# hat_v2.net
KiCad netlist of a schematic drawn in EAGLE
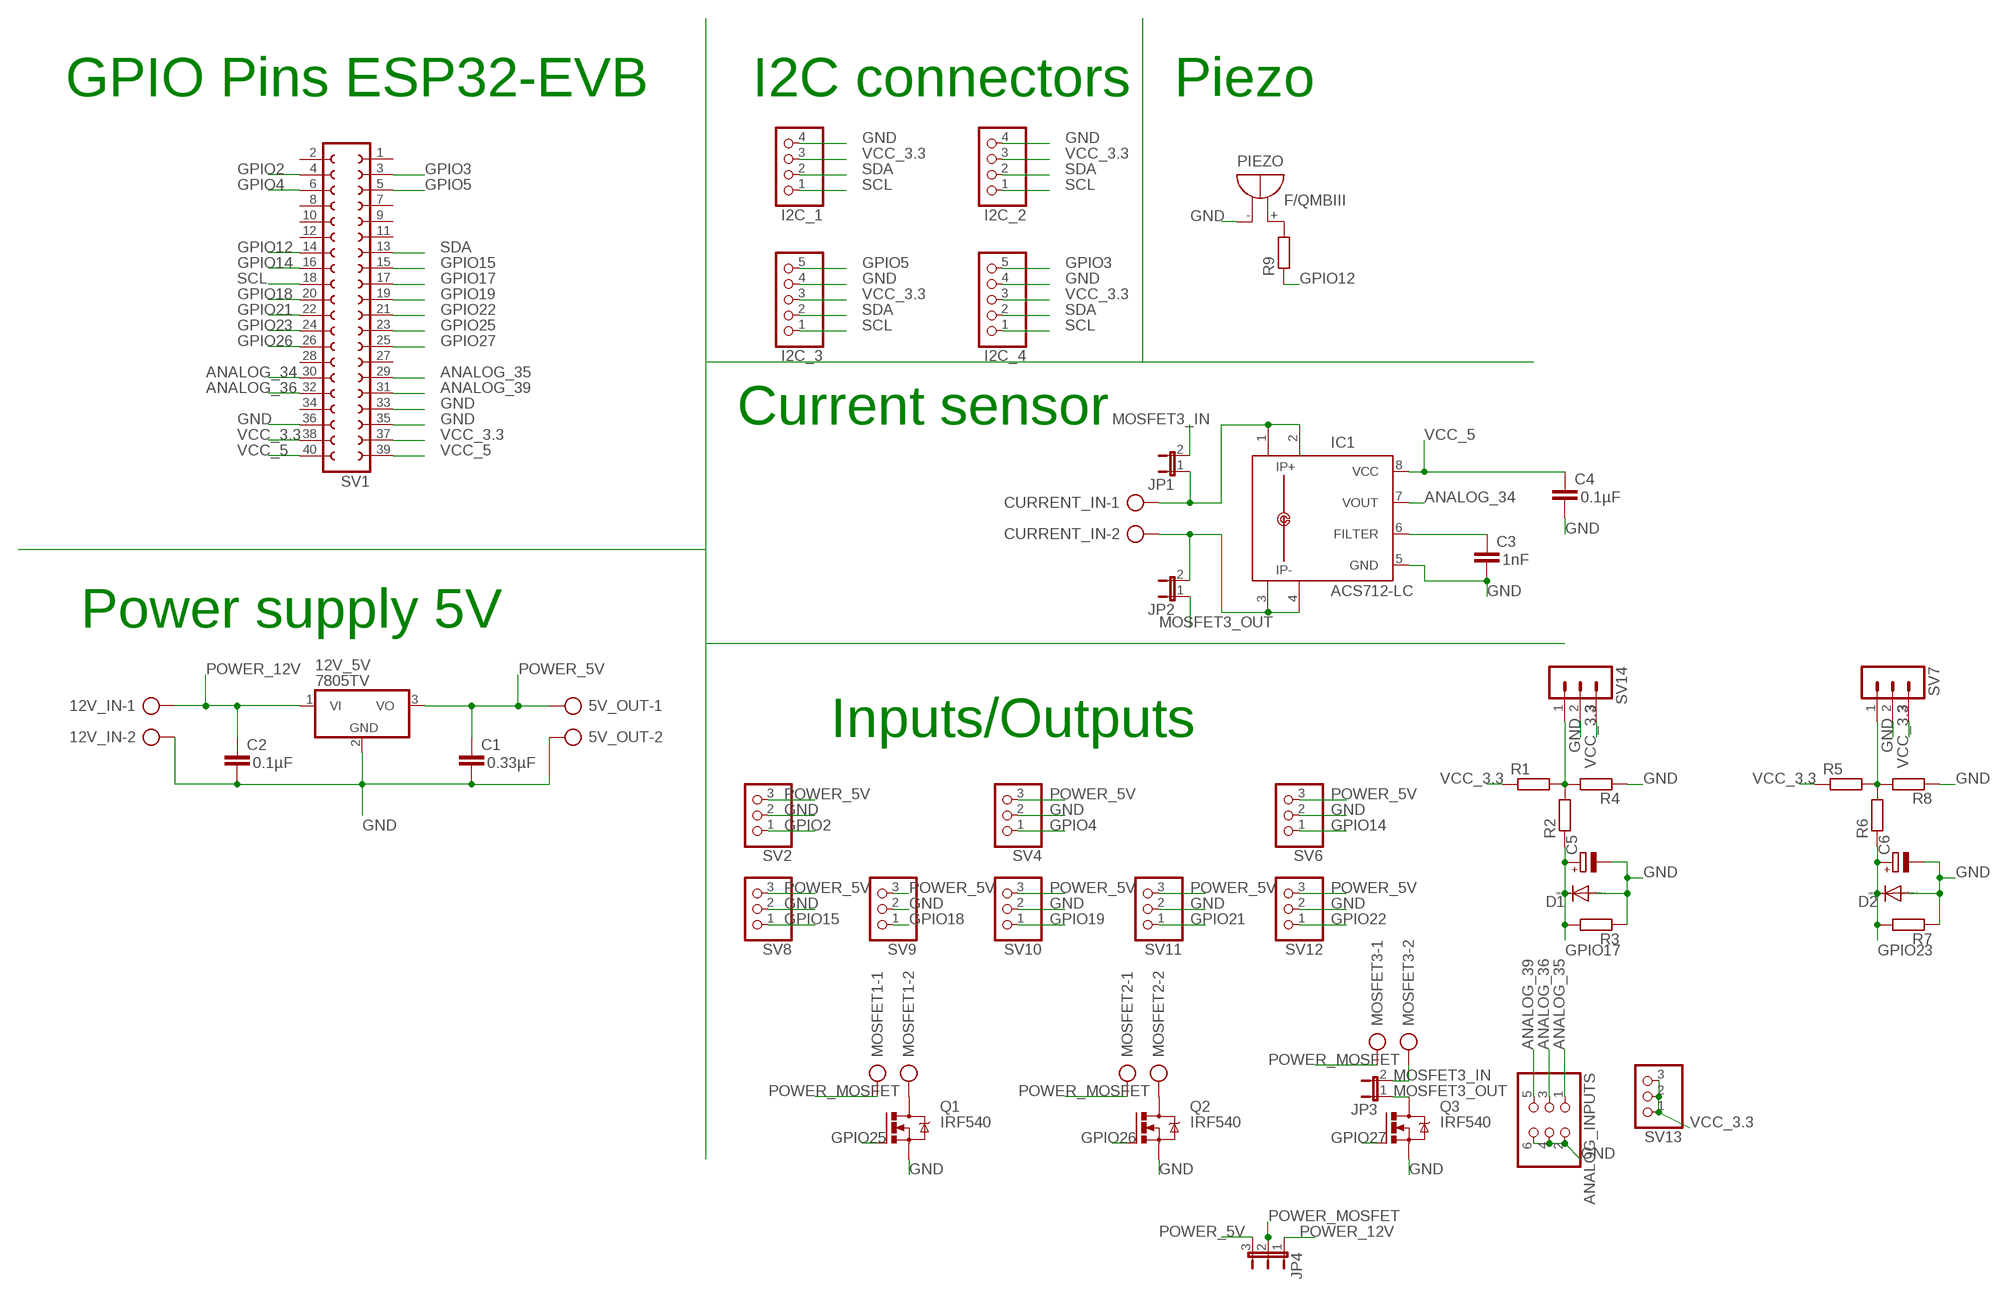
[diagram p0: schematic, sheet 1]

(export (version "E")
  (design (tool "Eeschema 10.0.6"))
  (components
    (comp (ref "5V_OUT")
      (value "AK500/2")
      (footprint "eagle-import:AK500_2")
      (libsource (lib "eagle-import") (part "AK500/2"))
    )
    (comp (ref "12V_5V")
      (value "7805TV")
      (footprint "eagle-import:TO220V")
      (libsource (lib "eagle-import") (part "78TV05"))
    )
    (comp (ref "12V_IN")
      (value "AK500/2")
      (footprint "eagle-import:AK500_2")
      (libsource (lib "eagle-import") (part "AK500/2"))
    )
    (comp (ref "ANALOG_INPUTS")
      (value "PINHD-2X3")
      (footprint "eagle-import:2X03")
      (libsource (lib "eagle-import") (part "PINHD-2X3"))
    )
    (comp (ref "C1")
      (value "C-EU050-050X075")
      (footprint "eagle-import:C050-050X075")
      (fields (field (name "C1") "0.33µF"))
      (libsource (lib "eagle-import") (part "resistor_348_C-EU050-050X075"))
    )
    (comp (ref "C2")
      (value "C-EU050-035X075")
      (footprint "eagle-import:C050-035X075")
      (fields (field (name "C2") "0.1µF"))
      (libsource (lib "eagle-import") (part "resistor_348_C-EU050-035X075"))
    )
    (comp (ref "C3")
      (value "C-EU025-025X050")
      (footprint "eagle-import:C025-025X050")
      (fields (field (name "SPICEPREFIX") "C") (field (name "SPICEPREFIX_1") "1nF"))
      (libsource (lib "eagle-import") (part "C-EU025-025X050"))
    )
    (comp (ref "C4")
      (value "C-EU025-025X050")
      (footprint "eagle-import:C025-025X050")
      (fields (field (name "SPICEPREFIX") "C") (field (name "SPICEPREFIX_1") "0.1µF"))
      (libsource (lib "eagle-import") (part "C-EU025-025X050"))
    )
    (comp (ref "C5")
      (value "CPOL-EUE2.5-6")
      (footprint "eagle-import:E2,5-6")
      (libsource (lib "eagle-import") (part "CPOL-EUE2.5-6"))
    )
    (comp (ref "C6")
      (value "CPOL-EUE2.5-6")
      (footprint "eagle-import:E2,5-6")
      (libsource (lib "eagle-import") (part "CPOL-EUE2.5-6"))
    )
    (comp (ref "CURRENT_IN")
      (value "AK500/2")
      (footprint "eagle-import:AK500_2")
      (libsource (lib "eagle-import") (part "AK500/2"))
    )
    (comp (ref "D1")
      (value "DIODE-C1702-05")
      (footprint "eagle-import:C1702-05")
      (libsource (lib "eagle-import") (part "DIODE-C1702-05"))
    )
    (comp (ref "D2")
      (value "DIODE-C1702-05")
      (footprint "eagle-import:C1702-05")
      (libsource (lib "eagle-import") (part "DIODE-C1702-05"))
    )
    (comp (ref "I2C_1")
      (value "PINHD-1X4")
      (footprint "eagle-import:1X04")
      (libsource (lib "eagle-import") (part "PINHD-1X4"))
    )
    (comp (ref "I2C_2")
      (value "PINHD-1X4")
      (footprint "eagle-import:1X04")
      (libsource (lib "eagle-import") (part "PINHD-1X4"))
    )
    (comp (ref "I2C_3")
      (value "PINHD-1X5")
      (footprint "eagle-import:1X05")
      (libsource (lib "eagle-import") (part "PINHD-1X5"))
    )
    (comp (ref "I2C_4")
      (value "PINHD-1X5")
      (footprint "eagle-import:1X05")
      (libsource (lib "eagle-import") (part "PINHD-1X5"))
    )
    (comp (ref "IC1")
      (value "ACS712-LC")
      (footprint "eagle-import:SOIC8")
      (libsource (lib "eagle-import") (part "ACS712-LC"))
    )
    (comp (ref "JP1")
      (value "JP1E")
      (footprint "eagle-import:JP1")
      (libsource (lib "eagle-import") (part "JP1E"))
    )
    (comp (ref "JP2")
      (value "JP1E")
      (footprint "eagle-import:JP1")
      (libsource (lib "eagle-import") (part "JP1E"))
    )
    (comp (ref "JP3")
      (value "JP1E")
      (footprint "eagle-import:JP1")
      (libsource (lib "eagle-import") (part "JP1E"))
    )
    (comp (ref "JP4")
      (value "JP2E")
      (footprint "eagle-import:JP2")
      (libsource (lib "eagle-import") (part "JP2E"))
    )
    (comp (ref "MOSFET1")
      (value "AK500/2")
      (footprint "eagle-import:AK500_2")
      (libsource (lib "eagle-import") (part "AK500/2"))
    )
    (comp (ref "MOSFET2")
      (value "AK500/2")
      (footprint "eagle-import:AK500_2")
      (libsource (lib "eagle-import") (part "AK500/2"))
    )
    (comp (ref "MOSFET3")
      (value "AK500/2")
      (footprint "eagle-import:AK500_2")
      (libsource (lib "eagle-import") (part "AK500/2"))
    )
    (comp (ref "PIEZO")
      (value "F/QMBIII")
      (footprint "eagle-import:F_QMBIII")
      (libsource (lib "eagle-import") (part "F/QMBIII"))
    )
    (comp (ref "Q1")
      (value "IRF540")
      (footprint "eagle-import:TO220BV")
      (libsource (lib "eagle-import") (part "IRF540"))
    )
    (comp (ref "Q2")
      (value "IRF540")
      (footprint "eagle-import:TO220BV")
      (libsource (lib "eagle-import") (part "IRF540"))
    )
    (comp (ref "Q3")
      (value "IRF540")
      (footprint "eagle-import:TO220BV")
      (libsource (lib "eagle-import") (part "IRF540"))
    )
    (comp (ref "R1")
      (value "R-EU_0207/2V")
      (footprint "eagle-import:0207_2V")
      (libsource (lib "eagle-import") (part "R-EU_0207/2V"))
    )
    (comp (ref "R2")
      (value "R-EU_0207/2V")
      (footprint "eagle-import:0207_2V")
      (libsource (lib "eagle-import") (part "R-EU_0207/2V"))
    )
    (comp (ref "R3")
      (value "R-EU_0207/2V")
      (footprint "eagle-import:0207_2V")
      (libsource (lib "eagle-import") (part "R-EU_0207/2V"))
    )
    (comp (ref "R4")
      (value "R-EU_0617/5V")
      (footprint "eagle-import:0617V")
      (libsource (lib "eagle-import") (part "R-EU_0617/5V"))
    )
    (comp (ref "R5")
      (value "R-EU_0207/2V")
      (footprint "eagle-import:0207_2V")
      (libsource (lib "eagle-import") (part "R-EU_0207/2V"))
    )
    (comp (ref "R6")
      (value "R-EU_0207/2V")
      (footprint "eagle-import:0207_2V")
      (libsource (lib "eagle-import") (part "R-EU_0207/2V"))
    )
    (comp (ref "R7")
      (value "R-EU_0207/2V")
      (footprint "eagle-import:0207_2V")
      (libsource (lib "eagle-import") (part "R-EU_0207/2V"))
    )
    (comp (ref "R8")
      (value "R-EU_0617/5V")
      (footprint "eagle-import:0617V")
      (libsource (lib "eagle-import") (part "R-EU_0617/5V"))
    )
    (comp (ref "R9")
      (value "R-EU_0207/5V")
      (footprint "eagle-import:0207_5V")
      (libsource (lib "eagle-import") (part "R-EU_0207/5V"))
    )
    (comp (ref "SV1")
      (value "FE20-2")
      (footprint "eagle-import:FE20-2")
      (libsource (lib "eagle-import") (part "FE20-2"))
    )
    (comp (ref "SV2")
      (value "PINHD-1X3")
      (footprint "eagle-import:1X03")
      (fields (field (name "SPICEPREFIX") "J"))
      (libsource (lib "eagle-import") (part "PINHD-1X3"))
    )
    (comp (ref "SV4")
      (value "PINHD-1X3")
      (footprint "eagle-import:1X03")
      (fields (field (name "SPICEPREFIX") "J"))
      (libsource (lib "eagle-import") (part "PINHD-1X3"))
    )
    (comp (ref "SV6")
      (value "PINHD-1X3")
      (footprint "eagle-import:1X03")
      (fields (field (name "SPICEPREFIX") "J"))
      (libsource (lib "eagle-import") (part "PINHD-1X3"))
    )
    (comp (ref "SV7")
      (value "MA03-1")
      (footprint "eagle-import:MA03-1")
      (fields (field (name "SPICEPREFIX") "J"))
      (libsource (lib "eagle-import") (part "MA03-1"))
    )
    (comp (ref "SV8")
      (value "PINHD-1X3")
      (footprint "eagle-import:1X03")
      (libsource (lib "eagle-import") (part "PINHD-1X3"))
    )
    (comp (ref "SV9")
      (value "PINHD-1X3")
      (footprint "eagle-import:1X03")
      (fields (field (name "SPICEPREFIX") "J"))
      (libsource (lib "eagle-import") (part "PINHD-1X3"))
    )
    (comp (ref "SV10")
      (value "PINHD-1X3")
      (footprint "eagle-import:1X03")
      (fields (field (name "SPICEPREFIX") "J"))
      (libsource (lib "eagle-import") (part "PINHD-1X3"))
    )
    (comp (ref "SV11")
      (value "PINHD-1X3")
      (footprint "eagle-import:1X03")
      (fields (field (name "SPICEPREFIX") "J"))
      (libsource (lib "eagle-import") (part "PINHD-1X3"))
    )
    (comp (ref "SV12")
      (value "PINHD-1X3")
      (footprint "eagle-import:1X03")
      (fields (field (name "SPICEPREFIX") "J"))
      (libsource (lib "eagle-import") (part "PINHD-1X3"))
    )
    (comp (ref "SV13")
      (value "PINHD-1X3")
      (footprint "eagle-import:1X03")
      (libsource (lib "eagle-import") (part "PINHD-1X3"))
    )
    (comp (ref "SV14")
      (value "MA03-1")
      (footprint "eagle-import:MA03-1")
      (fields (field (name "SPICEPREFIX") "J"))
      (libsource (lib "eagle-import") (part "MA03-1"))
    )
  )
  (nets
    (net (code "1") (name "/ANALOG_34") (class "Default")
      (node (ref "IC1") (pin "7") (pinfunction "VOUT_7") (pintype "output"))
      (node (ref "SV1") (pin "30") (pinfunction "30_30") (pintype "passive"))
    )
    (net (code "2") (name "/ANALOG_35") (class "Default")
      (node (ref "ANALOG_INPUTS") (pin "1") (pinfunction "1_1") (pintype "passive"))
      (node (ref "SV1") (pin "29") (pinfunction "29_29") (pintype "passive"))
    )
    (net (code "3") (name "/ANALOG_36") (class "Default")
      (node (ref "ANALOG_INPUTS") (pin "3") (pinfunction "3_3") (pintype "passive"))
      (node (ref "SV1") (pin "32") (pinfunction "32_32") (pintype "passive"))
    )
    (net (code "4") (name "/ANALOG_39") (class "Default")
      (node (ref "ANALOG_INPUTS") (pin "5") (pinfunction "5_5") (pintype "passive"))
      (node (ref "SV1") (pin "31") (pinfunction "31_31") (pintype "passive"))
    )
    (net (code "5") (name "/GND") (class "Default")
      (node (ref "12V_5V") (pin "2") (pinfunction "GND_2") (pintype "passive"))
      (node (ref "12V_IN") (pin "2") (pinfunction "KL_2") (pintype "passive"))
      (node (ref "5V_OUT") (pin "2") (pinfunction "KL_2") (pintype "passive"))
      (node (ref "ANALOG_INPUTS") (pin "2") (pinfunction "2_2") (pintype "passive"))
      (node (ref "ANALOG_INPUTS") (pin "4") (pinfunction "4_4") (pintype "passive"))
      (node (ref "ANALOG_INPUTS") (pin "6") (pinfunction "6_6") (pintype "passive"))
      (node (ref "C1") (pin "2") (pinfunction "2_2") (pintype "passive"))
      (node (ref "C2") (pin "2") (pinfunction "2_2") (pintype "passive"))
      (node (ref "C3") (pin "2") (pinfunction "2_2") (pintype "passive"))
      (node (ref "C4") (pin "2") (pinfunction "2_2") (pintype "passive"))
      (node (ref "C5") (pin "-") (pinfunction "-_-") (pintype "passive"))
      (node (ref "C6") (pin "-") (pinfunction "-_-") (pintype "passive"))
      (node (ref "D1") (pin "A") (pinfunction "A_A") (pintype "passive"))
      (node (ref "D2") (pin "A") (pinfunction "A_A") (pintype "passive"))
      (node (ref "I2C_1") (pin "4") (pinfunction "4_4") (pintype "passive"))
      (node (ref "I2C_2") (pin "4") (pinfunction "4_4") (pintype "passive"))
      (node (ref "I2C_3") (pin "4") (pinfunction "4_4") (pintype "passive"))
      (node (ref "I2C_4") (pin "4") (pinfunction "4_4") (pintype "passive"))
      (node (ref "IC1") (pin "5") (pinfunction "GND_5") (pintype "power_in"))
      (node (ref "PIEZO") (pin "-") (pinfunction "+_-") (pintype "passive"))
      (node (ref "Q1") (pin "S") (pinfunction "S_S") (pintype "passive"))
      (node (ref "Q2") (pin "S") (pinfunction "S_S") (pintype "passive"))
      (node (ref "Q3") (pin "S") (pinfunction "S_S") (pintype "passive"))
      (node (ref "R3") (pin "1") (pinfunction "1_1") (pintype "passive"))
      (node (ref "R4") (pin "1") (pinfunction "1_1") (pintype "passive"))
      (node (ref "R7") (pin "1") (pinfunction "1_1") (pintype "passive"))
      (node (ref "R8") (pin "1") (pinfunction "1_1") (pintype "passive"))
      (node (ref "SV1") (pin "33") (pinfunction "33_33") (pintype "passive"))
      (node (ref "SV1") (pin "35") (pinfunction "35_35") (pintype "passive"))
      (node (ref "SV1") (pin "36") (pinfunction "36_36") (pintype "passive"))
      (node (ref "SV10") (pin "2") (pinfunction "2_2") (pintype "passive"))
      (node (ref "SV11") (pin "2") (pinfunction "2_2") (pintype "passive"))
      (node (ref "SV12") (pin "2") (pinfunction "2_2") (pintype "passive"))
      (node (ref "SV14") (pin "2") (pinfunction "2_2") (pintype "passive"))
      (node (ref "SV2") (pin "2") (pinfunction "2_2") (pintype "passive"))
      (node (ref "SV4") (pin "2") (pinfunction "2_2") (pintype "passive"))
      (node (ref "SV6") (pin "2") (pinfunction "2_2") (pintype "passive"))
      (node (ref "SV7") (pin "2") (pinfunction "2_2") (pintype "passive"))
      (node (ref "SV8") (pin "2") (pinfunction "2_2") (pintype "passive"))
      (node (ref "SV9") (pin "2") (pinfunction "2_2") (pintype "passive"))
    )
    (net (code "6") (name "/GPIO2") (class "Default")
      (node (ref "SV1") (pin "4") (pinfunction "4_4") (pintype "passive"))
      (node (ref "SV2") (pin "1") (pinfunction "1_1") (pintype "passive"))
    )
    (net (code "7") (name "/GPIO3") (class "Default")
      (node (ref "I2C_4") (pin "5") (pinfunction "5_5") (pintype "passive"))
      (node (ref "SV1") (pin "3") (pinfunction "3_3") (pintype "passive"))
    )
    (net (code "8") (name "/GPIO4") (class "Default")
      (node (ref "SV1") (pin "6") (pinfunction "6_6") (pintype "passive"))
      (node (ref "SV4") (pin "1") (pinfunction "1_1") (pintype "passive"))
    )
    (net (code "9") (name "/GPIO5") (class "Default")
      (node (ref "I2C_3") (pin "5") (pinfunction "5_5") (pintype "passive"))
      (node (ref "SV1") (pin "5") (pinfunction "5_5") (pintype "passive"))
    )
    (net (code "10") (name "/GPIO12") (class "Default")
      (node (ref "R9") (pin "1") (pinfunction "1_1") (pintype "passive"))
      (node (ref "SV1") (pin "14") (pinfunction "14_14") (pintype "passive"))
    )
    (net (code "11") (name "/GPIO14") (class "Default")
      (node (ref "SV1") (pin "16") (pinfunction "16_16") (pintype "passive"))
      (node (ref "SV6") (pin "1") (pinfunction "1_1") (pintype "passive"))
    )
    (net (code "12") (name "/GPIO15") (class "Default")
      (node (ref "SV1") (pin "15") (pinfunction "15_15") (pintype "passive"))
      (node (ref "SV8") (pin "1") (pinfunction "1_1") (pintype "passive"))
    )
    (net (code "13") (name "/GPIO17") (class "Default")
      (node (ref "C5") (pin "+") (pinfunction "+_+") (pintype "passive"))
      (node (ref "D1") (pin "C") (pinfunction "C_C") (pintype "passive"))
      (node (ref "R2") (pin "1") (pinfunction "1_1") (pintype "passive"))
      (node (ref "R3") (pin "2") (pinfunction "2_2") (pintype "passive"))
      (node (ref "SV1") (pin "17") (pinfunction "17_17") (pintype "passive"))
    )
    (net (code "14") (name "/GPIO18") (class "Default")
      (node (ref "SV1") (pin "20") (pinfunction "20_20") (pintype "passive"))
      (node (ref "SV9") (pin "1") (pinfunction "1_1") (pintype "passive"))
    )
    (net (code "15") (name "/GPIO19") (class "Default")
      (node (ref "SV1") (pin "19") (pinfunction "19_19") (pintype "passive"))
      (node (ref "SV10") (pin "1") (pinfunction "1_1") (pintype "passive"))
    )
    (net (code "16") (name "/GPIO21") (class "Default")
      (node (ref "SV1") (pin "22") (pinfunction "22_22") (pintype "passive"))
      (node (ref "SV11") (pin "1") (pinfunction "1_1") (pintype "passive"))
    )
    (net (code "17") (name "/GPIO22") (class "Default")
      (node (ref "SV1") (pin "21") (pinfunction "21_21") (pintype "passive"))
      (node (ref "SV12") (pin "1") (pinfunction "1_1") (pintype "passive"))
    )
    (net (code "18") (name "/GPIO23") (class "Default")
      (node (ref "C6") (pin "+") (pinfunction "+_+") (pintype "passive"))
      (node (ref "D2") (pin "C") (pinfunction "C_C") (pintype "passive"))
      (node (ref "R6") (pin "1") (pinfunction "1_1") (pintype "passive"))
      (node (ref "R7") (pin "2") (pinfunction "2_2") (pintype "passive"))
      (node (ref "SV1") (pin "24") (pinfunction "24_24") (pintype "passive"))
    )
    (net (code "19") (name "/GPIO25") (class "Default")
      (node (ref "Q1") (pin "G") (pinfunction "G_G") (pintype "passive"))
      (node (ref "SV1") (pin "23") (pinfunction "23_23") (pintype "passive"))
    )
    (net (code "20") (name "/GPIO26") (class "Default")
      (node (ref "Q2") (pin "G") (pinfunction "G_G") (pintype "passive"))
      (node (ref "SV1") (pin "26") (pinfunction "26_26") (pintype "passive"))
    )
    (net (code "21") (name "/GPIO27") (class "Default")
      (node (ref "Q3") (pin "G") (pinfunction "G_G") (pintype "passive"))
      (node (ref "SV1") (pin "25") (pinfunction "25_25") (pintype "passive"))
    )
    (net (code "22") (name "/MOSFET3_IN") (class "Default")
      (node (ref "JP1") (pin "2") (pinfunction "2_2") (pintype "passive"))
      (node (ref "JP3") (pin "2") (pinfunction "2_2") (pintype "passive"))
      (node (ref "MOSFET3") (pin "2") (pinfunction "KL_2") (pintype "passive"))
    )
    (net (code "23") (name "/MOSFET3_OUT") (class "Default")
      (node (ref "JP2") (pin "1") (pinfunction "1_1") (pintype "passive"))
      (node (ref "JP3") (pin "1") (pinfunction "1_1") (pintype "passive"))
      (node (ref "Q3") (pin "D") (pinfunction "D_D") (pintype "passive"))
    )
    (net (code "24") (name "/POWER_5V") (class "Default")
      (node (ref "12V_5V") (pin "3") (pinfunction "VO_3") (pintype "passive"))
      (node (ref "5V_OUT") (pin "1") (pinfunction "KL_1") (pintype "passive"))
      (node (ref "C1") (pin "1") (pinfunction "1_1") (pintype "passive"))
      (node (ref "JP4") (pin "3") (pinfunction "3_3") (pintype "passive"))
      (node (ref "SV10") (pin "3") (pinfunction "3_3") (pintype "passive"))
      (node (ref "SV11") (pin "3") (pinfunction "3_3") (pintype "passive"))
      (node (ref "SV12") (pin "3") (pinfunction "3_3") (pintype "passive"))
      (node (ref "SV2") (pin "3") (pinfunction "3_3") (pintype "passive"))
      (node (ref "SV4") (pin "3") (pinfunction "3_3") (pintype "passive"))
      (node (ref "SV6") (pin "3") (pinfunction "3_3") (pintype "passive"))
      (node (ref "SV8") (pin "3") (pinfunction "3_3") (pintype "passive"))
      (node (ref "SV9") (pin "3") (pinfunction "3_3") (pintype "passive"))
    )
    (net (code "25") (name "/POWER_12V") (class "Default")
      (node (ref "12V_5V") (pin "1") (pinfunction "VI_1") (pintype "input"))
      (node (ref "12V_IN") (pin "1") (pinfunction "KL_1") (pintype "passive"))
      (node (ref "C2") (pin "1") (pinfunction "1_1") (pintype "passive"))
      (node (ref "JP4") (pin "1") (pinfunction "1_1") (pintype "passive"))
    )
    (net (code "26") (name "/POWER_MOSFET") (class "Default")
      (node (ref "JP4") (pin "2") (pinfunction "2_2") (pintype "passive"))
      (node (ref "MOSFET1") (pin "1") (pinfunction "KL_1") (pintype "passive"))
      (node (ref "MOSFET2") (pin "1") (pinfunction "KL_1") (pintype "passive"))
      (node (ref "MOSFET3") (pin "1") (pinfunction "KL_1") (pintype "passive"))
    )
    (net (code "27") (name "/SCL") (class "Default")
      (node (ref "I2C_1") (pin "1") (pinfunction "1_1") (pintype "passive"))
      (node (ref "I2C_2") (pin "1") (pinfunction "1_1") (pintype "passive"))
      (node (ref "I2C_3") (pin "1") (pinfunction "1_1") (pintype "passive"))
      (node (ref "I2C_4") (pin "1") (pinfunction "1_1") (pintype "passive"))
      (node (ref "SV1") (pin "18") (pinfunction "18_18") (pintype "passive"))
    )
    (net (code "28") (name "/SDA") (class "Default")
      (node (ref "I2C_1") (pin "2") (pinfunction "2_2") (pintype "passive"))
      (node (ref "I2C_2") (pin "2") (pinfunction "2_2") (pintype "passive"))
      (node (ref "I2C_3") (pin "2") (pinfunction "2_2") (pintype "passive"))
      (node (ref "I2C_4") (pin "2") (pinfunction "2_2") (pintype "passive"))
      (node (ref "SV1") (pin "13") (pinfunction "13_13") (pintype "passive"))
    )
    (net (code "29") (name "/VCC_3.3") (class "Default")
      (node (ref "I2C_1") (pin "3") (pinfunction "3_3") (pintype "passive"))
      (node (ref "I2C_2") (pin "3") (pinfunction "3_3") (pintype "passive"))
      (node (ref "I2C_3") (pin "3") (pinfunction "3_3") (pintype "passive"))
      (node (ref "I2C_4") (pin "3") (pinfunction "3_3") (pintype "passive"))
      (node (ref "R1") (pin "1") (pinfunction "1_1") (pintype "passive"))
      (node (ref "R5") (pin "1") (pinfunction "1_1") (pintype "passive"))
      (node (ref "SV1") (pin "37") (pinfunction "37_37") (pintype "passive"))
      (node (ref "SV1") (pin "38") (pinfunction "38_38") (pintype "passive"))
      (node (ref "SV13") (pin "1") (pinfunction "1_1") (pintype "passive"))
      (node (ref "SV13") (pin "2") (pinfunction "2_2") (pintype "passive"))
      (node (ref "SV13") (pin "3") (pinfunction "3_3") (pintype "passive"))
      (node (ref "SV14") (pin "3") (pinfunction "3_3") (pintype "passive"))
      (node (ref "SV7") (pin "3") (pinfunction "3_3") (pintype "passive"))
    )
    (net (code "30") (name "/VCC_5") (class "Default")
      (node (ref "C4") (pin "1") (pinfunction "1_1") (pintype "passive"))
      (node (ref "IC1") (pin "8") (pinfunction "VCC_8") (pintype "power_in"))
      (node (ref "SV1") (pin "39") (pinfunction "39_39") (pintype "passive"))
      (node (ref "SV1") (pin "40") (pinfunction "40_40") (pintype "passive"))
    )
    (net (code "31") (name "Net-(CURRENT_INA-KL)") (class "Default")
      (node (ref "CURRENT_IN") (pin "1") (pinfunction "KL_1") (pintype "passive"))
      (node (ref "IC1") (pin "1") (pinfunction "IP+_1") (pintype "passive"))
      (node (ref "IC1") (pin "2") (pinfunction "IP+1_2") (pintype "passive"))
      (node (ref "JP1") (pin "1") (pinfunction "1_1") (pintype "passive"))
    )
    (net (code "32") (name "Net-(CURRENT_INB-KL)") (class "Default")
      (node (ref "CURRENT_IN") (pin "2") (pinfunction "KL_2") (pintype "passive"))
      (node (ref "IC1") (pin "3") (pinfunction "IP-_3") (pintype "passive"))
      (node (ref "IC1") (pin "4") (pinfunction "IP-1_4") (pintype "passive"))
      (node (ref "JP2") (pin "2") (pinfunction "2_2") (pintype "passive"))
    )
    (net (code "33") (name "Net-(IC1-FILTER)") (class "Default")
      (node (ref "C3") (pin "1") (pinfunction "1_1") (pintype "passive"))
      (node (ref "IC1") (pin "6") (pinfunction "FILTER_6") (pintype "bidirectional"))
    )
    (net (code "34") (name "Net-(MOSFET1B-KL)") (class "Default")
      (node (ref "MOSFET1") (pin "2") (pinfunction "KL_2") (pintype "passive"))
      (node (ref "Q1") (pin "D") (pinfunction "D_D") (pintype "passive"))
    )
    (net (code "35") (name "Net-(MOSFET2B-KL)") (class "Default")
      (node (ref "MOSFET2") (pin "2") (pinfunction "KL_2") (pintype "passive"))
      (node (ref "Q2") (pin "D") (pinfunction "D_D") (pintype "passive"))
    )
    (net (code "36") (name "Net-(PIEZO--)") (class "Default")
      (node (ref "PIEZO") (pin "+") (pinfunction "-_+") (pintype "passive"))
      (node (ref "R9") (pin "2") (pinfunction "2_2") (pintype "passive"))
    )
    (net (code "37") (name "Net-(R1-Pad2)") (class "Default")
      (node (ref "R1") (pin "2") (pinfunction "2_2") (pintype "passive"))
      (node (ref "R2") (pin "2") (pinfunction "2_2") (pintype "passive"))
      (node (ref "R4") (pin "2") (pinfunction "2_2") (pintype "passive"))
      (node (ref "SV14") (pin "1") (pinfunction "1_1") (pintype "passive"))
    )
    (net (code "38") (name "Net-(R5-Pad2)") (class "Default")
      (node (ref "R5") (pin "2") (pinfunction "2_2") (pintype "passive"))
      (node (ref "R6") (pin "2") (pinfunction "2_2") (pintype "passive"))
      (node (ref "R8") (pin "2") (pinfunction "2_2") (pintype "passive"))
      (node (ref "SV7") (pin "1") (pinfunction "1_1") (pintype "passive"))
    )
    (net (code "39") (name "unconnected-(SV1-Pad1)") (class "Default")
      (node (ref "SV1") (pin "1") (pinfunction "1_1") (pintype "passive"))
    )
    (net (code "40") (name "unconnected-(SV1-Pad2)") (class "Default")
      (node (ref "SV1") (pin "2") (pinfunction "2_2") (pintype "passive"))
    )
    (net (code "41") (name "unconnected-(SV1-Pad7)") (class "Default")
      (node (ref "SV1") (pin "7") (pinfunction "7_7") (pintype "passive"))
    )
    (net (code "42") (name "unconnected-(SV1-Pad8)") (class "Default")
      (node (ref "SV1") (pin "8") (pinfunction "8_8") (pintype "passive"))
    )
    (net (code "43") (name "unconnected-(SV1-Pad9)") (class "Default")
      (node (ref "SV1") (pin "9") (pinfunction "9_9") (pintype "passive"))
    )
    (net (code "44") (name "unconnected-(SV1-Pad10)") (class "Default")
      (node (ref "SV1") (pin "10") (pinfunction "10_10") (pintype "passive"))
    )
    (net (code "45") (name "unconnected-(SV1-Pad11)") (class "Default")
      (node (ref "SV1") (pin "11") (pinfunction "11_11") (pintype "passive"))
    )
    (net (code "46") (name "unconnected-(SV1-Pad12)") (class "Default")
      (node (ref "SV1") (pin "12") (pinfunction "12_12") (pintype "passive"))
    )
    (net (code "47") (name "unconnected-(SV1-Pad27)") (class "Default")
      (node (ref "SV1") (pin "27") (pinfunction "27_27") (pintype "passive"))
    )
    (net (code "48") (name "unconnected-(SV1-Pad28)") (class "Default")
      (node (ref "SV1") (pin "28") (pinfunction "28_28") (pintype "passive"))
    )
    (net (code "49") (name "unconnected-(SV1-Pad34)") (class "Default")
      (node (ref "SV1") (pin "34") (pinfunction "34_34") (pintype "passive"))
    )
  )
)
